# VFD25650.net
KiCad netlist of a schematic drawn in Altium Designer
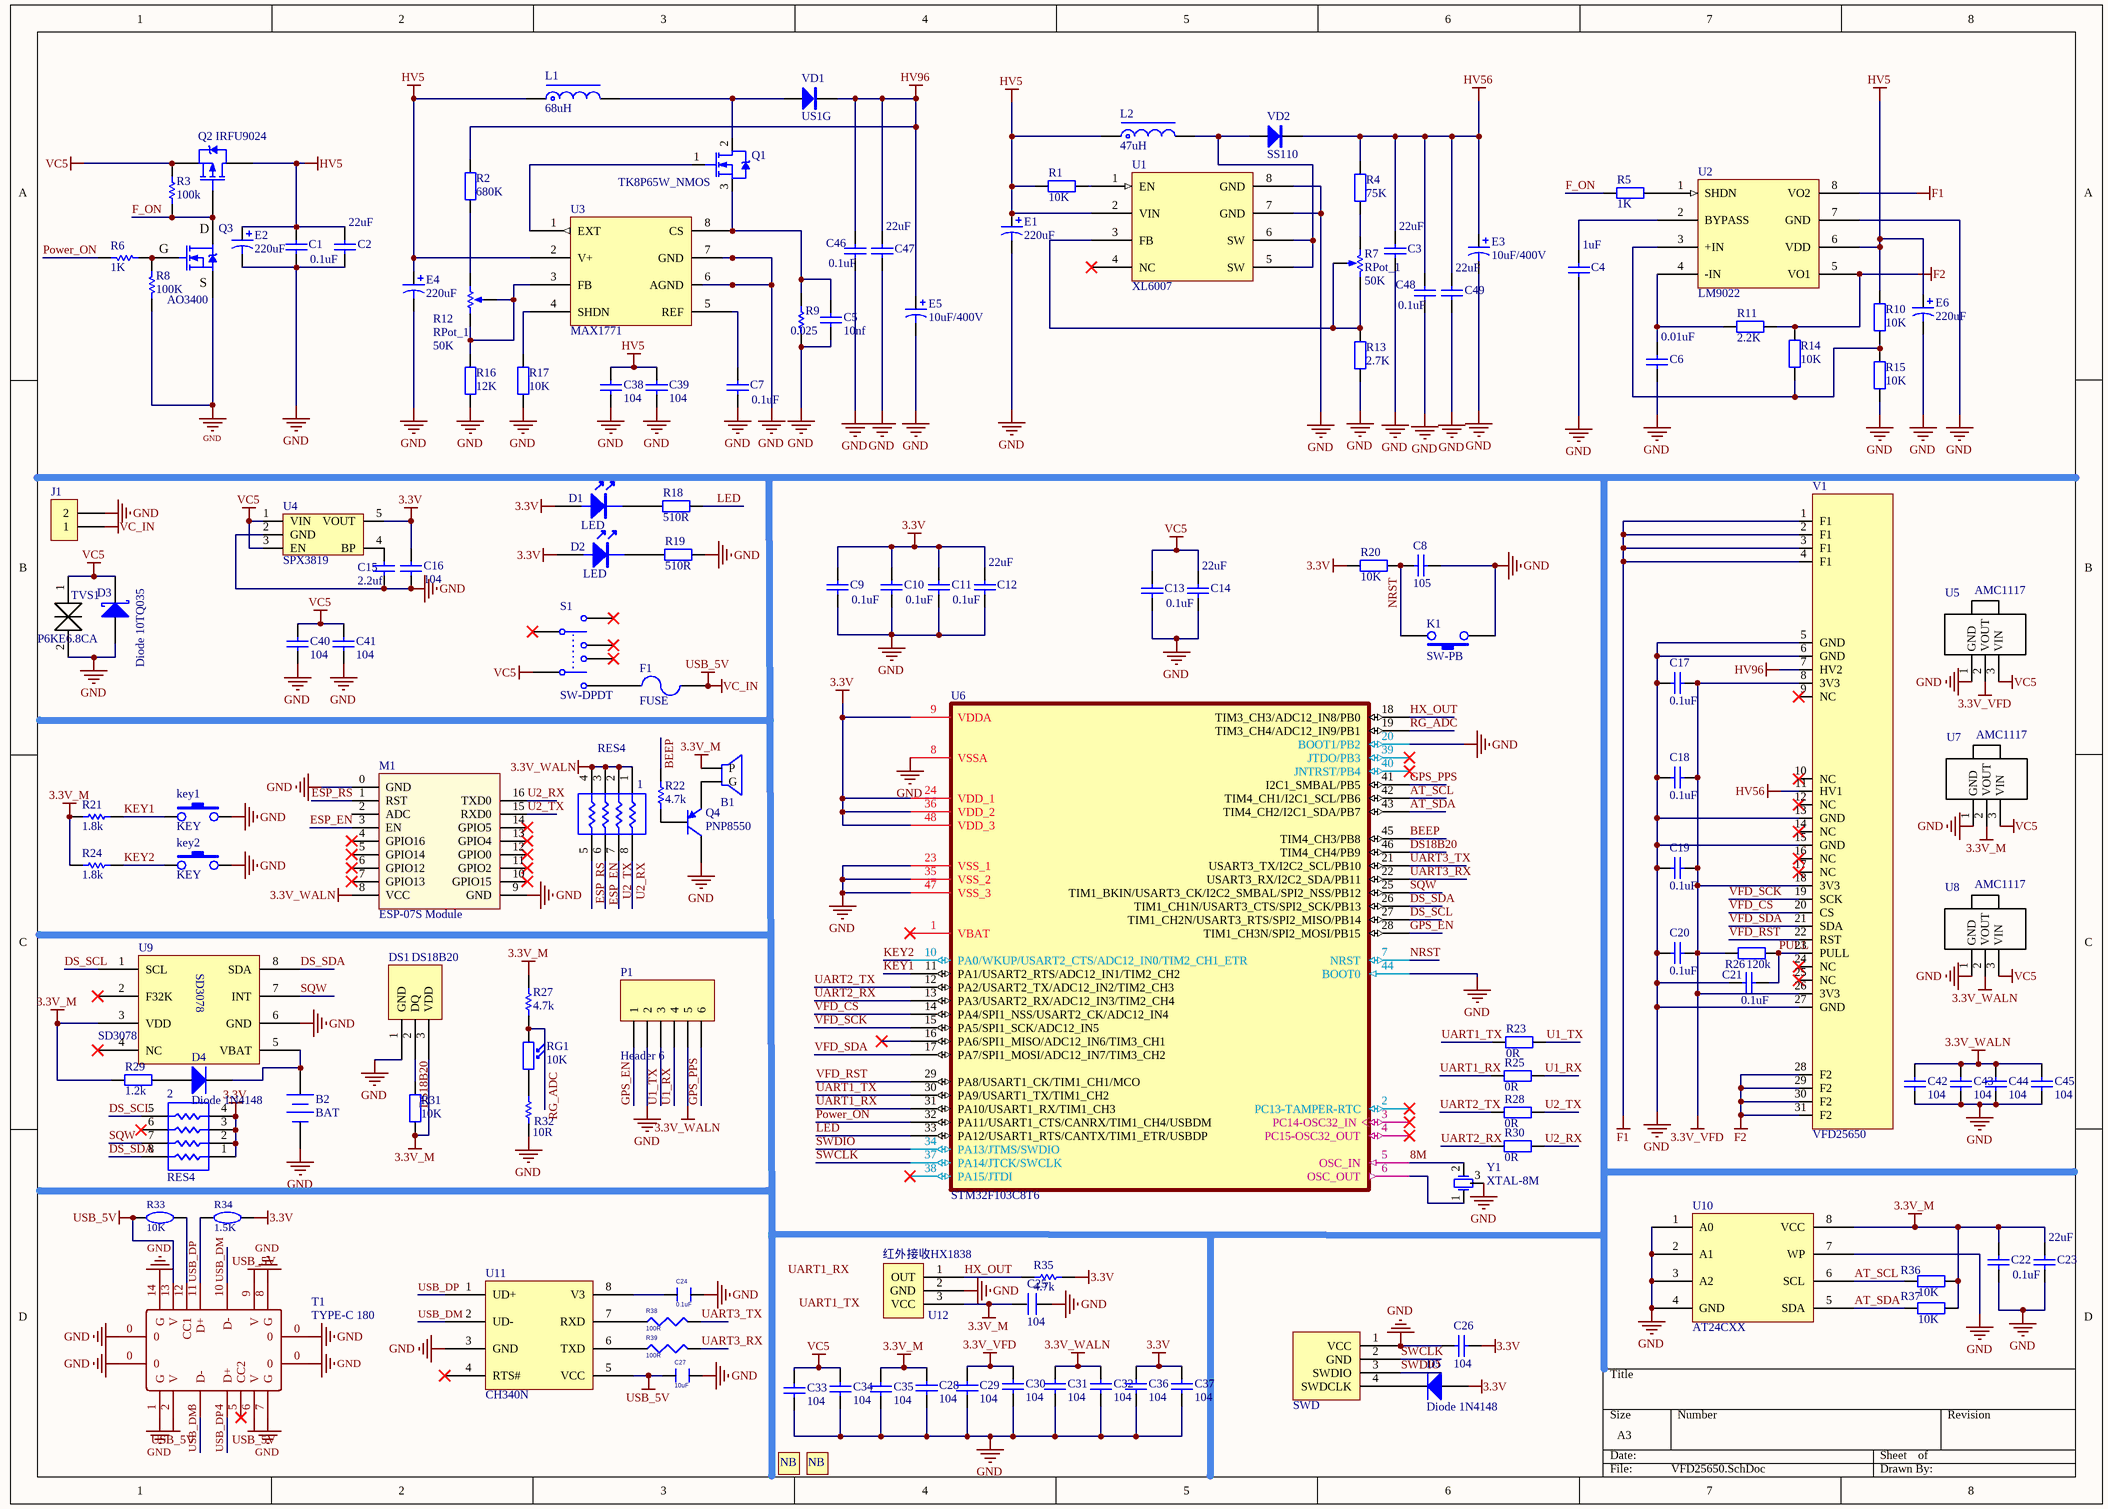
[diagram p0: VFD25650.SchDoc]

(export (version "E")
  (design (tool "Eeschema 10.0.6"))
  (components
    (comp (ref "1") (value "RES4") (footprint "0603RES") (libsource (lib "鲸落") (part "RES4")))
    (comp (ref "2") (value "RES4") (footprint "0603RES") (libsource (lib "鲸落") (part "RES4")))
    (comp (ref "B1") (value "BEEP") (footprint "BELL-SMALL") (libsource (lib "Mlia") (part "BEEP")))
    (comp (ref "B2") (value "BAT") (footprint "CR2032_B") (libsource (lib "Mlia") (part "BAT")))
    (comp (ref "C1")
      (value "0.1uF")
      (footprint "0603C")
      (description "Capacitor")
      (fields (field (name "Comment") "Cap") (field (name "PUBLISHER") "Altium Limited"))
      (libsource (lib "Miscellaneous Devices") (part "Cap"))
    )
    (comp (ref "C2")
      (value "22uF")
      (footprint "0603C")
      (description "Capacitor")
      (fields (field (name "Comment") "Cap") (field (name "PUBLISHER") "Altium Limited"))
      (libsource (lib "Miscellaneous Devices") (part "Cap"))
    )
    (comp (ref "C3")
      (value "22uF")
      (footprint "0603C")
      (description "Capacitor")
      (fields (field (name "Comment") "Cap") (field (name "PUBLISHER") "Altium Limited"))
      (libsource (lib "Miscellaneous Devices") (part "Cap"))
    )
    (comp (ref "C4")
      (value "1uF")
      (footprint "0603C")
      (description "Capacitor")
      (fields (field (name "Comment") "Cap") (field (name "PUBLISHER") "Altium Limited"))
      (libsource (lib "Miscellaneous Devices") (part "Cap"))
    )
    (comp (ref "C5")
      (value "10nf")
      (footprint "C 0603")
      (description "贴片电容")
      (fields (field (name "PUBLISHER") "Altium Limited"))
      (libsource (lib "Miscellaneous Devices") (part "Cap"))
    )
    (comp (ref "C6")
      (value "0.01uF")
      (footprint "0603C")
      (description "Capacitor")
      (fields (field (name "Comment") "Cap") (field (name "PUBLISHER") "Altium Limited"))
      (libsource (lib "Miscellaneous Devices") (part "Cap"))
    )
    (comp (ref "C7")
      (value "0.1uF")
      (footprint "0603C")
      (description "Capacitor")
      (fields (field (name "Comment") "Cap") (field (name "PUBLISHER") "Altium Limited"))
      (libsource (lib "Miscellaneous Devices") (part "Cap"))
    )
    (comp (ref "C8")
      (value "105")
      (footprint "0603C")
      (description "Capacitor")
      (fields (field (name "PUBLISHER") "Altium Limited"))
      (libsource (lib "STM32F103C8T6") (part "Cap"))
    )
    (comp (ref "C9")
      (value "0.1uF")
      (footprint "0603C")
      (description "Capacitor")
      (fields (field (name "Comment") "Cap") (field (name "PUBLISHER") "Altium Limited"))
      (libsource (lib "Miscellaneous Devices") (part "Cap"))
    )
    (comp (ref "C10")
      (value "0.1uF")
      (footprint "0603C")
      (description "Capacitor")
      (fields (field (name "Comment") "Cap") (field (name "PUBLISHER") "Altium Limited"))
      (libsource (lib "Miscellaneous Devices") (part "Cap"))
    )
    (comp (ref "C11")
      (value "0.1uF")
      (footprint "0603C")
      (description "Capacitor")
      (fields (field (name "Comment") "Cap") (field (name "PUBLISHER") "Altium Limited"))
      (libsource (lib "Miscellaneous Devices") (part "Cap"))
    )
    (comp (ref "C12")
      (value "22uF")
      (footprint "0603C")
      (description "Capacitor")
      (fields (field (name "Comment") "Cap") (field (name "PUBLISHER") "Altium Limited"))
      (libsource (lib "Miscellaneous Devices") (part "Cap"))
    )
    (comp (ref "C13")
      (value "0.1uF")
      (footprint "0603C")
      (description "Capacitor")
      (fields (field (name "Comment") "Cap") (field (name "PUBLISHER") "Altium Limited"))
      (libsource (lib "Miscellaneous Devices") (part "Cap"))
    )
    (comp (ref "C14")
      (value "22uF")
      (footprint "0603C")
      (description "Capacitor")
      (fields (field (name "Comment") "Cap") (field (name "PUBLISHER") "Altium Limited"))
      (libsource (lib "Miscellaneous Devices") (part "Cap"))
    )
    (comp (ref "C15")
      (value "2.2uf")
      (footprint "0603C")
      (description "Polarized Capacitor (Radial)")
      (fields (field (name "Comment") "Cap") (field (name "PUBLISHER") "Altium Limited"))
      (libsource (lib "Fantasy") (part "Cap"))
    )
    (comp (ref "C16")
      (value "104")
      (footprint "0603C")
      (description "Polarized Capacitor (Radial)")
      (fields (field (name "Comment") "Cap") (field (name "PUBLISHER") "Altium Limited"))
      (libsource (lib "Fantasy") (part "Cap"))
    )
    (comp (ref "C17")
      (value "0.1uF")
      (footprint "0603C")
      (description "Capacitor")
      (fields (field (name "Comment") "Cap") (field (name "PUBLISHER") "Altium Limited"))
      (libsource (lib "Miscellaneous Devices") (part "Cap"))
    )
    (comp (ref "C18")
      (value "0.1uF")
      (footprint "0603C")
      (description "Capacitor")
      (fields (field (name "Comment") "Cap") (field (name "PUBLISHER") "Altium Limited"))
      (libsource (lib "Miscellaneous Devices") (part "Cap"))
    )
    (comp (ref "C19")
      (value "0.1uF")
      (footprint "0603C")
      (description "Capacitor")
      (fields (field (name "Comment") "Cap") (field (name "PUBLISHER") "Altium Limited"))
      (libsource (lib "Miscellaneous Devices") (part "Cap"))
    )
    (comp (ref "C20")
      (value "0.1uF")
      (footprint "0603C")
      (description "Capacitor")
      (fields (field (name "Comment") "Cap") (field (name "PUBLISHER") "Altium Limited"))
      (libsource (lib "Miscellaneous Devices") (part "Cap"))
    )
    (comp (ref "C21")
      (value "0.1uF")
      (footprint "0603C")
      (description "Capacitor")
      (fields (field (name "Comment") "Cap") (field (name "PUBLISHER") "Altium Limited"))
      (libsource (lib "Miscellaneous Devices") (part "Cap"))
    )
    (comp (ref "C22")
      (value "0.1uF")
      (footprint "0603C")
      (description "Capacitor")
      (fields (field (name "Comment") "Cap") (field (name "PUBLISHER") "Altium Limited"))
      (libsource (lib "Miscellaneous Devices") (part "Cap"))
    )
    (comp (ref "C23")
      (value "22uF")
      (footprint "0603C")
      (description "Capacitor")
      (fields (field (name "Comment") "Cap") (field (name "PUBLISHER") "Altium Limited"))
      (libsource (lib "Miscellaneous Devices") (part "Cap"))
    )
    (comp (ref "C24")
      (value "0.1uF")
      (footprint "C 0603")
      (description "CAP ±20%/6.3V/X5R/SMT0402")
      (libsource (lib "*") (part "CAPACITOR"))
    )
    (comp (ref "C25") (value "104") (footprint "0603C") (libsource (lib "Mlia") (part "0603C")))
    (comp (ref "C26")
      (value "104")
      (footprint "0603C")
      (description "Capacitor")
      (fields (field (name "PUBLISHER") "Altium Limited"))
      (libsource (lib "STM32F103C8T6") (part "Cap"))
    )
    (comp (ref "C27")
      (value "10uF")
      (footprint "C 0603")
      (description "CAP ±20%/10V/X5R/SMT0603")
      (libsource (lib "*") (part "CAPACITOR"))
    )
    (comp (ref "C28")
      (value "104")
      (footprint "0603C")
      (description "无极性电容")
      (fields (field (name "Comment") "Cap") (field (name "PUBLISHER") "Altium Limited"))
      (libsource (lib "Fszhang") (part "Cap"))
    )
    (comp (ref "C29")
      (value "104")
      (footprint "0603C")
      (description "无极性电容")
      (fields (field (name "Comment") "Cap") (field (name "PUBLISHER") "Altium Limited"))
      (libsource (lib "Fszhang") (part "Cap"))
    )
    (comp (ref "C30")
      (value "104")
      (footprint "0603C")
      (description "无极性电容")
      (fields (field (name "Comment") "Cap") (field (name "PUBLISHER") "Altium Limited"))
      (libsource (lib "Fszhang") (part "Cap"))
    )
    (comp (ref "C31")
      (value "104")
      (footprint "0603C")
      (description "无极性电容")
      (fields (field (name "Comment") "Cap") (field (name "PUBLISHER") "Altium Limited"))
      (libsource (lib "Fszhang") (part "Cap"))
    )
    (comp (ref "C32")
      (value "104")
      (footprint "0603C")
      (description "无极性电容")
      (fields (field (name "Comment") "Cap") (field (name "PUBLISHER") "Altium Limited"))
      (libsource (lib "Fszhang") (part "Cap"))
    )
    (comp (ref "C33")
      (value "104")
      (footprint "0603C")
      (description "无极性电容")
      (fields (field (name "Comment") "Cap") (field (name "PUBLISHER") "Altium Limited"))
      (libsource (lib "Fszhang") (part "Cap"))
    )
    (comp (ref "C34")
      (value "104")
      (footprint "0603C")
      (description "无极性电容")
      (fields (field (name "Comment") "Cap") (field (name "PUBLISHER") "Altium Limited"))
      (libsource (lib "Fszhang") (part "Cap"))
    )
    (comp (ref "C35")
      (value "104")
      (footprint "0603C")
      (description "无极性电容")
      (fields (field (name "Comment") "Cap") (field (name "PUBLISHER") "Altium Limited"))
      (libsource (lib "Fszhang") (part "Cap"))
    )
    (comp (ref "C36")
      (value "104")
      (footprint "0603C")
      (description "无极性电容")
      (fields (field (name "Comment") "Cap") (field (name "PUBLISHER") "Altium Limited"))
      (libsource (lib "Fszhang") (part "Cap"))
    )
    (comp (ref "C37")
      (value "104")
      (footprint "0603C")
      (description "无极性电容")
      (fields (field (name "Comment") "Cap") (field (name "PUBLISHER") "Altium Limited"))
      (libsource (lib "Fszhang") (part "Cap"))
    )
    (comp (ref "C38")
      (value "104")
      (footprint "0603C")
      (description "无极性电容")
      (fields (field (name "Comment") "Cap") (field (name "PUBLISHER") "Altium Limited"))
      (libsource (lib "Fszhang") (part "Cap"))
    )
    (comp (ref "C39")
      (value "104")
      (footprint "0603C")
      (description "无极性电容")
      (fields (field (name "Comment") "Cap") (field (name "PUBLISHER") "Altium Limited"))
      (libsource (lib "Fszhang") (part "Cap"))
    )
    (comp (ref "C40")
      (value "104")
      (footprint "0603C")
      (description "无极性电容")
      (fields (field (name "Comment") "Cap") (field (name "PUBLISHER") "Altium Limited"))
      (libsource (lib "Fszhang") (part "Cap"))
    )
    (comp (ref "C41")
      (value "104")
      (footprint "0603C")
      (description "无极性电容")
      (fields (field (name "Comment") "Cap") (field (name "PUBLISHER") "Altium Limited"))
      (libsource (lib "Fszhang") (part "Cap"))
    )
    (comp (ref "C42")
      (value "104")
      (footprint "0603C")
      (description "无极性电容")
      (fields (field (name "Comment") "Cap") (field (name "PUBLISHER") "Altium Limited"))
      (libsource (lib "Fszhang") (part "Cap"))
    )
    (comp (ref "C43")
      (value "104")
      (footprint "0603C")
      (description "无极性电容")
      (fields (field (name "Comment") "Cap") (field (name "PUBLISHER") "Altium Limited"))
      (libsource (lib "Fszhang") (part "Cap"))
    )
    (comp (ref "C44")
      (value "104")
      (footprint "0603C")
      (description "无极性电容")
      (fields (field (name "Comment") "Cap") (field (name "PUBLISHER") "Altium Limited"))
      (libsource (lib "Fszhang") (part "Cap"))
    )
    (comp (ref "C45")
      (value "104")
      (footprint "0603C")
      (description "无极性电容")
      (fields (field (name "Comment") "Cap") (field (name "PUBLISHER") "Altium Limited"))
      (libsource (lib "Fszhang") (part "Cap"))
    )
    (comp (ref "C46")
      (value "0.1uF")
      (footprint "0805C")
      (description "Capacitor")
      (fields (field (name "Comment") "Cap") (field (name "PUBLISHER") "Altium Limited"))
      (libsource (lib "Miscellaneous Devices") (part "Cap"))
    )
    (comp (ref "C47")
      (value "22uF")
      (footprint "0805C")
      (description "Capacitor")
      (fields (field (name "Comment") "Cap") (field (name "PUBLISHER") "Altium Limited"))
      (libsource (lib "Miscellaneous Devices") (part "Cap"))
    )
    (comp (ref "C48")
      (value "0.1uF")
      (footprint "0805C")
      (description "Capacitor")
      (fields (field (name "Comment") "Cap") (field (name "PUBLISHER") "Altium Limited"))
      (libsource (lib "Miscellaneous Devices") (part "Cap"))
    )
    (comp (ref "C49")
      (value "22uF")
      (footprint "0805C")
      (description "Capacitor")
      (fields (field (name "Comment") "Cap") (field (name "PUBLISHER") "Altium Limited"))
      (libsource (lib "Miscellaneous Devices") (part "Cap"))
    )
    (comp (ref "D1") (value "LED") (footprint "LED 0805B") (libsource (lib "STM32F103C8T6") (part "LED")))
    (comp (ref "D2") (value "LED") (footprint "LED 0603R") (libsource (lib "STM32F103C8T6") (part "LED")))
    (comp (ref "D3")
      (value "Diode 10TQ035")
      (footprint "SOD-123")
      (description "Schottky Rectifier")
      (fields (field (name "PUBLISHER") "Altium Limited"))
      (libsource (lib "Miscellaneous Devices") (part "Diode 10TQ035"))
    )
    (comp (ref "D4")
      (value "Diode 1N4148")
      (footprint "SOD-323")
      (description "High Conductance Fast Diode")
      (fields (field (name "PUBLISHER") "Altium Limited"))
      (libsource (lib "LONG_lclr") (part "Diode 1N4148"))
    )
    (comp (ref "D5")
      (value "Diode 1N4148")
      (footprint "SOD-323")
      (description "High Conductance Fast Diode")
      (fields (field (name "PUBLISHER") "Altium Limited"))
      (libsource (lib "LONG_lclr") (part "Diode 1N4148"))
    )
    (comp (ref "DS1")
      (value "DS18B20")
      (footprint "HDR-1X3")
      (description "温度传感器")
      (libsource (lib "Fszhang") (part "DS18B20"))
    )
    (comp (ref "E1")
      (value "220uF")
      (footprint "CM D(6.3*5.4)")
      (description "Polarized Capacitor (Radial)")
      (fields (field (name "Comment") "Cap Pol1") (field (name "PUBLISHER") "Altium Limited"))
      (libsource (lib "Miscellaneous Devices") (part "Cap Pol1"))
    )
    (comp (ref "E2")
      (value "220uF")
      (footprint "CM D(6.3*5.4)")
      (description "Polarized Capacitor (Radial)")
      (fields (field (name "Comment") "Cap Pol1") (field (name "PUBLISHER") "Altium Limited"))
      (libsource (lib "Miscellaneous Devices") (part "Cap Pol1"))
    )
    (comp (ref "E3")
      (value "10uF/400V")
      (footprint "CM D(6.3*5.4)")
      (description "Polarized Capacitor (Radial)")
      (fields (field (name "Comment") "Cap Pol1") (field (name "PUBLISHER") "Altium Limited"))
      (libsource (lib "Miscellaneous Devices") (part "Cap Pol1"))
    )
    (comp (ref "E4")
      (value "220uF")
      (footprint "CM D(6.3*5.4)")
      (description "Polarized Capacitor (Radial)")
      (fields (field (name "Comment") "Cap Pol1") (field (name "PUBLISHER") "Altium Limited"))
      (libsource (lib "Miscellaneous Devices") (part "Cap Pol1"))
    )
    (comp (ref "E5")
      (value "10uF/400V")
      (footprint "CM D(6.3*5.4)")
      (description "Polarized Capacitor (Radial)")
      (fields (field (name "Comment") "Cap Pol1") (field (name "PUBLISHER") "Altium Limited"))
      (libsource (lib "Miscellaneous Devices") (part "Cap Pol1"))
    )
    (comp (ref "E6")
      (value "220uF")
      (footprint "CM D(6.3*5.4)")
      (description "Polarized Capacitor (Radial)")
      (fields (field (name "Comment") "Cap Pol1") (field (name "PUBLISHER") "Altium Limited"))
      (libsource (lib "Miscellaneous Devices") (part "Cap Pol1"))
    )
    (comp (ref "F1") (value "FUSE") (footprint "FU 0805") (libsource (lib "Mlia") (part "FUSE")))
    (comp (ref "J1")
      (value "CON2")
      (footprint "DC-012")
      (description "Connector")
      (libsource (lib "*") (part "CON2"))
    )
    (comp (ref "K1") (value "SW-PB") (footprint "KEY_M") (libsource (lib "*") (part "SW-PB")))
    (comp (ref "key1") (value "KEY") (footprint "TSW DIP-6*6*7_V") (libsource (lib "LONG_lclr") (part "KEY")))
    (comp (ref "key2") (value "KEY") (footprint "TSW DIP-6*6*7_V") (libsource (lib "LONG_lclr") (part "KEY")))
    (comp (ref "L1")
      (value "68uH")
      (footprint "CDRH73")
      (description "工字电感")
      (fields (field (name "版权归属") "源创客"))
      (libsource (lib "3D Mode") (part "L-PK"))
    )
    (comp (ref "L2")
      (value "47uH")
      (footprint "CDRH73")
      (description "工字电感")
      (fields (field (name "版权归属") "源创客"))
      (libsource (lib "3D Mode") (part "L-PK"))
    )
    (comp (ref "M1")
      (value "ESP-07S Module")
      (footprint "ESP-07S Module")
      (libsource (lib "LONG_lclr") (part "ESP-07S Module"))
    )
    (comp (ref "P1")
      (value "Header 6")
      (footprint "LONG_lclr:1.25-6p")
      (description "Header, 6-Pin")
      (fields (field (name "PUBLISHER") "Altium Limited"))
      (libsource (lib "Miscellaneous Connectors") (part "Header 6"))
    )
    (comp (ref "picture1") (value "图标") (footprint "rapter") (libsource (lib "LONG_lclr") (part "SP")))
    (comp (ref "picture2") (value "图标") (footprint "LCL") (libsource (lib "LONG_lclr") (part "SP")))
    (comp (ref "Q1") (value "TK8P65W_NMOS") (footprint "TO252") (libsource (lib "Mlia") (part "IR7843_NMOS")))
    (comp (ref "Q2")
      (value "IRFU9024")
      (footprint "TO252 - duplicate")
      (description "P-Channel Power MOSFET")
      (fields (field (name "PUBLISHER") "Altium Limited"))
      (libsource (lib "LONG_lclr") (part "PMOS-2"))
    )
    (comp (ref "Q3")
      (value "AO3400")
      (footprint "MMBT3906")
      (description "N沟场效应管 贴片SOT23-3")
      (fields (field (name "版权归属") "源创客"))
      (libsource (lib "3D Mode") (part "2SK3615"))
    )
    (comp (ref "Q4") (value "PNP8550") (footprint "NPN8050 SOT23R") (libsource (lib "Mlia") (part "PNP8550")))
    (comp (ref "R1")
      (value "10K")
      (footprint "0805R")
      (description "Resistor")
      (fields (field (name "PUBLISHER") "Altium Limited"))
      (libsource (lib "STM32F103C8T6") (part "Res2"))
    )
    (comp (ref "R2")
      (value "680K")
      (footprint "0805R")
      (description "Resistor")
      (fields (field (name "PUBLISHER") "Altium Limited"))
      (libsource (lib "") (part "Res2_3"))
    )
    (comp (ref "R3") (value "100k") (footprint "0805R") (libsource (lib "Mlia") (part "0603r")))
    (comp (ref "R4")
      (value "75K")
      (footprint "0805R")
      (description "Resistor")
      (fields (field (name "PUBLISHER") "Altium Limited"))
      (libsource (lib "") (part "Res2_3"))
    )
    (comp (ref "R5")
      (value "1K")
      (footprint "0805R")
      (description "Resistor")
      (fields (field (name "PUBLISHER") "Altium Limited"))
      (libsource (lib "STM32F103C8T6") (part "Res2"))
    )
    (comp (ref "R6")
      (value "1K")
      (footprint "0603R")
      (description "贴片电阻 0603")
      (fields (field (name "PUBLISHER") "Altium Limited"))
      (libsource (lib "Miscellaneous Devices") (part "Res1"))
    )
    (comp (ref "R7")
      (value "RPot_1")
      (footprint "RPart")
      (description "Potentiometer")
      (fields (field (name "ALTIUM_VALUE") "50K") (field (name "PUBLISHER") "Altium Limited"))
      (libsource (lib "LONG_lclr") (part "RPot_1"))
    )
    (comp (ref "R8")
      (value "100K")
      (footprint "0603R")
      (description "贴片电阻 0603")
      (fields (field (name "PUBLISHER") "Altium Limited"))
      (libsource (lib "Miscellaneous Devices") (part "Res1"))
    )
    (comp (ref "R9")
      (value "0.025")
      (footprint "RES 1206")
      (description "贴片电阻")
      (fields (field (name "PUBLISHER") "Altium Limited"))
      (libsource (lib "Miscellaneous Devices") (part "Res1"))
    )
    (comp (ref "R10")
      (value "10K")
      (footprint "0805R")
      (description "Resistor")
      (fields (field (name "PUBLISHER") "Altium Limited"))
      (libsource (lib "") (part "Res2_3"))
    )
    (comp (ref "R11")
      (value "2.2K")
      (footprint "0805R")
      (description "Resistor")
      (fields (field (name "PUBLISHER") "Altium Limited"))
      (libsource (lib "STM32F103C8T6") (part "Res2"))
    )
    (comp (ref "R12")
      (value "RPot_1")
      (footprint "RPart")
      (description "Potentiometer")
      (fields (field (name "ALTIUM_VALUE") "50K") (field (name "PUBLISHER") "Altium Limited"))
      (libsource (lib "LONG_lclr") (part "RPot_1"))
    )
    (comp (ref "R13")
      (value "2.7K")
      (footprint "0805R")
      (description "Resistor")
      (fields (field (name "PUBLISHER") "Altium Limited"))
      (libsource (lib "") (part "Res2_3"))
    )
    (comp (ref "R14")
      (value "10K")
      (footprint "0805R")
      (description "Resistor")
      (fields (field (name "PUBLISHER") "Altium Limited"))
      (libsource (lib "") (part "Res2_3"))
    )
    (comp (ref "R15")
      (value "10K")
      (footprint "0805R")
      (description "Resistor")
      (fields (field (name "PUBLISHER") "Altium Limited"))
      (libsource (lib "") (part "Res2_2"))
    )
    (comp (ref "R16")
      (value "12K")
      (footprint "0805R")
      (description "Resistor")
      (fields (field (name "PUBLISHER") "Altium Limited"))
      (libsource (lib "") (part "Res2_3"))
    )
    (comp (ref "R17")
      (value "10K")
      (footprint "0603R")
      (description "Resistor")
      (fields (field (name "PUBLISHER") "Altium Limited"))
      (libsource (lib "") (part "Res2_2"))
    )
    (comp (ref "R18")
      (value "510R")
      (footprint "0603R")
      (description "Resistor")
      (fields (field (name "PUBLISHER") "Altium Limited"))
      (libsource (lib "") (part "Res2_1"))
    )
    (comp (ref "R19")
      (value "510R")
      (footprint "0603R")
      (description "Resistor")
      (fields (field (name "PUBLISHER") "Altium Limited"))
      (libsource (lib "") (part "Res2_1"))
    )
    (comp (ref "R20")
      (value "10K")
      (footprint "0603R")
      (description "Resistor")
      (fields (field (name "PUBLISHER") "Altium Limited"))
      (libsource (lib "STM32F103C8T6") (part "Res2"))
    )
    (comp (ref "R21") (value "1.8k") (footprint "0603R") (libsource (lib "Mlia") (part "0603r")))
    (comp (ref "R22") (value "4.7k") (footprint "0603R") (libsource (lib "Mlia") (part "0603r")))
    (comp (ref "R23")
      (value "0R")
      (footprint "0805R")
      (description "Resistor")
      (fields (field (name "PUBLISHER") "Altium Limited"))
      (libsource (lib "") (part "Res2_1"))
    )
    (comp (ref "R24") (value "1.8k") (footprint "0603R") (libsource (lib "Mlia") (part "0603r")))
    (comp (ref "R25")
      (value "0R")
      (footprint "0805R")
      (description "Resistor")
      (fields (field (name "PUBLISHER") "Altium Limited"))
      (libsource (lib "") (part "Res2_1"))
    )
    (comp (ref "R26")
      (value "120k")
      (footprint "R 0603")
      (description "Resistor")
      (fields (field (name "PUBLISHER") "Altium Limited"))
      (libsource (lib "") (part "Res2_1"))
    )
    (comp (ref "R27") (value "4.7k") (footprint "0603R") (libsource (lib "Mlia") (part "0603r")))
    (comp (ref "R28")
      (value "0R")
      (footprint "0805R")
      (description "Resistor")
      (fields (field (name "PUBLISHER") "Altium Limited"))
      (libsource (lib "") (part "Res2_1"))
    )
    (comp (ref "R29")
      (value "1.2k")
      (footprint "0603R")
      (description "贴片电阻")
      (fields (field (name "Comment") "Res1") (field (name "PUBLISHER") "Altium Limited"))
      (libsource (lib "") (part "Res1_1"))
    )
    (comp (ref "R30")
      (value "0R")
      (footprint "0805R")
      (description "Resistor")
      (fields (field (name "PUBLISHER") "Altium Limited"))
      (libsource (lib "") (part "Res2_1"))
    )
    (comp (ref "R31")
      (value "10K")
      (footprint "0603R")
      (description "贴片电阻")
      (fields (field (name "Comment") "Res1") (field (name "PUBLISHER") "Altium Limited"))
      (libsource (lib "Fszhang") (part "Res1"))
    )
    (comp (ref "R32") (value "10R") (footprint "0603R") (libsource (lib "Mlia") (part "0603r")))
    (comp (ref "R33")
      (value "1A保险丝")
      (footprint "R 0603")
      (fields (field (name "COMMENT_1") "10K") (field (name "PUBLISHER") "Altium Limited"))
      (libsource (lib "altium-import") (part "root_2_10K_"))
    )
    (comp (ref "R34")
      (value "1K")
      (footprint "R 0603")
      (fields (field (name "COMMENT_1") "1.5K") (field (name "PUBLISHER") "Altium Limited"))
      (libsource (lib "altium-import") (part "root_2_1.5K_"))
    )
    (comp (ref "R35") (value "4.7k") (footprint "0603R") (libsource (lib "Mlia") (part "0603r")))
    (comp (ref "R36")
      (value "10K")
      (footprint "0603R")
      (description "Resistor")
      (fields (field (name "PUBLISHER") "Altium Limited"))
      (libsource (lib "STM32F103C8T6") (part "Res2"))
    )
    (comp (ref "R37")
      (value "10K")
      (footprint "0603R")
      (description "Resistor")
      (fields (field (name "PUBLISHER") "Altium Limited"))
      (libsource (lib "STM32F103C8T6") (part "Res2"))
    )
    (comp (ref "R38")
      (value "100R")
      (footprint "R 0603")
      (description "RES 1/16W 5% SMT0402")
      (libsource (lib "*") (part "R_Dup1"))
    )
    (comp (ref "R39")
      (value "100R")
      (footprint "R 0603")
      (description "RES 1/16W 5% SMT0402")
      (libsource (lib "*") (part "R_Dup1"))
    )
    (comp (ref "RG1")
      (value "10K")
      (footprint "RG5528")
      (description "光敏电阻")
      (fields (field (name "版权归属") "源创客"))
      (libsource (lib "3D Mode") (part "RG5528"))
    )
    (comp (ref "S1")
      (value "SW-DPDT")
      (footprint "SWitch - duplicate1")
      (description "Double-Pole, Double-Throw Switch")
      (fields (field (name "PUBLISHER") "Altium Limited"))
      (libsource (lib "鲸落") (part "SW-DPDT"))
    )
    (comp (ref "SWD1") (value "SWD") (footprint "1.25-4p") (libsource (lib "自创") (part "SWD")))
    (comp (ref "T1")
      (value "TYPE-C 180")
      (footprint "type-c 180")
      (libsource (lib "LONG_lclr") (part "TYPE-C 180"))
    )
    (comp (ref "TVS1") (value "P6KE6.8CA") (footprint "SMB") (libsource (lib "VFDClock") (part "P6KE6.8CA")))
    (comp (ref "U1") (value "XL6007") (footprint "SOP8_N") (libsource (lib "LONG_lclr") (part "XL6007")))
    (comp (ref "U2") (value "LM9022") (footprint "SOP8_N") (libsource (lib "LONG_lclr") (part "LM9022")))
    (comp (ref "U3") (value "MAX1771") (footprint "SOP8_N") (libsource (lib "LONG_lclr") (part "MAX1771")))
    (comp (ref "U4")
      (value "SPX3819")
      (footprint "SOT23-5N")
      (description "3.3V超低压差LDO")
      (libsource (lib "Fantasy") (part "RT9193-33"))
    )
    (comp (ref "U5")
      (value "AMC1117")
      (footprint "AMS1117_SOT223")
      (libsource (lib "VFDClock") (part "AMC1117"))
    )
    (comp (ref "U6")
      (value "STM32F103C8T6")
      (footprint "LQFP48 7X7_L")
      (description "STM32 ARM-based 32-bit MCU with 64 Kbytes Flash, 48-pin LQFP, Industrial Temperature")
      (fields (field (name "PUBLISHER") "*"))
      (libsource (lib "stm32") (part "STM32F103C8T6"))
    )
    (comp (ref "U7")
      (value "AMC1117")
      (footprint "AMS1117_SOT223")
      (libsource (lib "VFDClock") (part "AMC1117"))
    )
    (comp (ref "U8")
      (value "AMC1117")
      (footprint "AMS1117_SOT223")
      (libsource (lib "VFDClock") (part "AMC1117"))
    )
    (comp (ref "U9") (value "SD3078") (footprint "SOP8W_L") (libsource (lib "LONG_lclr") (part "SD3078")))
    (comp (ref "U10") (value "AT24CXX") (footprint "SOP8_N") (libsource (lib "LONG_lclr") (part "AT24CXX")))
    (comp (ref "U11") (value "CH340N") (footprint "SOP8_N") (libsource (lib "LONG_lclr") (part "CH340N")))
    (comp (ref "U12")
      (value "红外接收HX1838")
      (footprint "红外HX1838")
      (libsource (lib "Mlia") (part "红外接收HX1838"))
    )
    (comp (ref "V1")
      (value "VFD25650")
      (footprint "VFD-25650")
      (libsource (lib "LONG_lclr") (part "VFD25650"))
    )
    (comp (ref "VD1")
      (value "US1G")
      (footprint "SMA")
      (description "肖特基二极管")
      (fields (field (name "版权归属") "源创客"))
      (libsource (lib "3D Mode") (part "SS14"))
    )
    (comp (ref "VD2")
      (value "SS110")
      (footprint "SMA")
      (description "肖特基二极管")
      (fields (field (name "版权归属") "源创客"))
      (libsource (lib "3D Mode") (part "SS14"))
    )
    (comp (ref "Y1") (value "XTAL-8M") (footprint "XTAL_8M") (libsource (lib "Mlia") (part "XTAL-8M")))
  )
  (nets
    (net (code "1") (name "/8M") (class "Default")
      (node (ref "U6") (pin "5") (pinfunction "OSC_IN_5") (pintype "input"))
      (node (ref "Y1") (pin "2") (pinfunction "OSC2_2") (pintype "passive"))
    )
    (net (code "2") (name "/AT_SCL") (class "Default")
      (node (ref "R36") (pin "2") (pinfunction "2_2") (pintype "passive"))
      (node (ref "U10") (pin "6") (pinfunction "SCL_6") (pintype "passive"))
      (node (ref "U6") (pin "42") (pinfunction "TIM4_CH1/I2C1_SCL/PB6_42") (pintype "bidirectional"))
    )
    (net (code "3") (name "/AT_SDA") (class "Default")
      (node (ref "R37") (pin "2") (pinfunction "2_2") (pintype "passive"))
      (node (ref "U10") (pin "5") (pinfunction "SDA_5") (pintype "passive"))
      (node (ref "U6") (pin "43") (pinfunction "TIM4_CH2/I2C1_SDA/PB7_43") (pintype "bidirectional"))
    )
    (net (code "4") (name "/BEEP") (class "Default")
      (node (ref "R22") (pin "2") (pinfunction "2_2") (pintype "passive"))
      (node (ref "U6") (pin "45") (pinfunction "TIM4_CH3/PB8_45") (pintype "bidirectional"))
    )
    (net (code "5") (name "/DS18B20") (class "Default")
      (node (ref "DS1") (pin "2") (pinfunction "DQ_2") (pintype "passive"))
      (node (ref "R31") (pin "1") (pinfunction "1_1") (pintype "passive"))
      (node (ref "U6") (pin "46") (pinfunction "TIM4_CH4/PB9_46") (pintype "bidirectional"))
    )
    (net (code "6") (name "/DS_SCL") (class "Default")
      (node (ref "2") (pin "5") (pinfunction "5_5") (pintype "passive"))
      (node (ref "U6") (pin "27") (pinfunction "TIM1_CH2N/USART3_RTS/SPI2_MISO/PB14_27") (pintype "bidirectional"))
      (node (ref "U9") (pin "1") (pinfunction "SCL_1") (pintype "passive"))
    )
    (net (code "7") (name "/DS_SDA") (class "Default")
      (node (ref "2") (pin "8") (pinfunction "8_8") (pintype "passive"))
      (node (ref "U6") (pin "26") (pinfunction "TIM1_CH1N/USART3_CTS/SPI2_SCK/PB13_26") (pintype "bidirectional"))
      (node (ref "U9") (pin "8") (pinfunction "SDA_8") (pintype "passive"))
    )
    (net (code "8") (name "/ESP_EN") (class "Default")
      (node (ref "1") (pin "6") (pinfunction "6_6") (pintype "passive"))
      (node (ref "M1") (pin "3") (pinfunction "EN_3") (pintype "passive"))
    )
    (net (code "9") (name "/ESP_RS") (class "Default")
      (node (ref "1") (pin "5") (pinfunction "5_5") (pintype "passive"))
      (node (ref "M1") (pin "1") (pinfunction "RST_1") (pintype "passive"))
    )
    (net (code "10") (name "/F_ON") (class "Default")
      (node (ref "Q2") (pin "1") (pinfunction "G_1") (pintype "passive"))
      (node (ref "Q3") (pin "3") (pinfunction "S_3") (pintype "passive"))
      (node (ref "R3") (pin "1") (pinfunction "1_1") (pintype "passive"))
      (node (ref "R5") (pin "2") (pinfunction "2_2") (pintype "passive"))
    )
    (net (code "11") (name "/GPS_EN") (class "Default")
      (node (ref "P1") (pin "1") (pinfunction "1_1") (pintype "passive"))
      (node (ref "U6") (pin "28") (pinfunction "TIM1_CH3N/SPI2_MOSI/PB15_28") (pintype "bidirectional"))
    )
    (net (code "12") (name "/GPS_PPS") (class "Default")
      (node (ref "P1") (pin "6") (pinfunction "6_6") (pintype "passive"))
      (node (ref "U6") (pin "41") (pinfunction "I2C1_SMBAL/PB5_41") (pintype "bidirectional"))
    )
    (net (code "13") (name "/HX_OUT") (class "Default")
      (node (ref "R35") (pin "1") (pinfunction "1_1") (pintype "passive"))
      (node (ref "U12") (pin "1") (pinfunction "OUT_1") (pintype "passive"))
      (node (ref "U6") (pin "18") (pinfunction "TIM3_CH3/ADC12_IN8/PB0_18") (pintype "bidirectional"))
    )
    (net (code "14") (name "/KEY1") (class "Default")
      (node (ref "R21") (pin "2") (pinfunction "2_2") (pintype "passive"))
      (node (ref "U6") (pin "11") (pinfunction "PA1/USART2_RTS/ADC12_IN1/TIM2_CH2_11") (pintype "bidirectional"))
      (node (ref "key1") (pin "1") (pinfunction "1_1") (pintype "passive"))
    )
    (net (code "15") (name "/KEY2") (class "Default")
      (node (ref "R24") (pin "2") (pinfunction "2_2") (pintype "passive"))
      (node (ref "U6") (pin "10") (pinfunction "PA0/WKUP/USART2_CTS/ADC12_IN0/TIM2_CH1_ETR_10") (pintype "bidirectional"))
      (node (ref "key2") (pin "1") (pinfunction "1_1") (pintype "passive"))
    )
    (net (code "16") (name "/LED") (class "Default")
      (node (ref "R18") (pin "2") (pinfunction "2_2") (pintype "passive"))
      (node (ref "U6") (pin "33") (pinfunction "PA12/USART1_RTS/CANTX/TIM1_ETR/USBDP_33") (pintype "bidirectional"))
    )
    (net (code "17") (name "/NRST") (class "Default")
      (node (ref "C8") (pin "2") (pinfunction "2_2") (pintype "passive"))
      (node (ref "K1") (pin "2") (pinfunction "2_2") (pintype "passive"))
      (node (ref "R20") (pin "1") (pinfunction "1_1") (pintype "passive"))
      (node (ref "U6") (pin "7") (pinfunction "NRST_7") (pintype "bidirectional"))
    )
    (net (code "18") (name "/PULL") (class "Default")
      (node (ref "C21") (pin "1") (pinfunction "1_1") (pintype "passive"))
      (node (ref "R26") (pin "2") (pinfunction "2_2") (pintype "passive"))
      (node (ref "V1") (pin "23") (pinfunction "PULL_23") (pintype "passive"))
    )
    (net (code "19") (name "/Power_ON") (class "Default")
      (node (ref "R6") (pin "2") (pinfunction "2_2") (pintype "passive"))
      (node (ref "U6") (pin "32") (pinfunction "PA11/USART1_CTS/CANRX/TIM1_CH4/USBDM_32") (pintype "bidirectional"))
    )
    (net (code "20") (name "/RG_ADC") (class "Default")
      (node (ref "R27") (pin "2") (pinfunction "2_2") (pintype "passive"))
      (node (ref "RG1") (pin "1") (pinfunction "1_1") (pintype "passive"))
      (node (ref "U6") (pin "19") (pinfunction "TIM3_CH4/ADC12_IN9/PB1_19") (pintype "bidirectional"))
    )
    (net (code "21") (name "/SQW") (class "Default")
      (node (ref "2") (pin "7") (pinfunction "7_7") (pintype "passive"))
      (node (ref "U6") (pin "25") (pinfunction "TIM1_BKIN/USART3_CK/I2C2_SMBAL/SPI2_NSS/PB12_25") (pintype "bidirectional"))
      (node (ref "U9") (pin "7") (pinfunction "INT_7") (pintype "passive"))
    )
    (net (code "22") (name "/SWCLK") (class "Default")
      (node (ref "SWD1") (pin "2") (pinfunction "GND_2") (pintype "passive"))
      (node (ref "U6") (pin "37") (pinfunction "PA14/JTCK/SWCLK_37") (pintype "bidirectional"))
    )
    (net (code "23") (name "/SWDIO") (class "Default")
      (node (ref "SWD1") (pin "3") (pinfunction "SWDIO_3") (pintype "passive"))
      (node (ref "U6") (pin "34") (pinfunction "PA13/JTMS/SWDIO_34") (pintype "bidirectional"))
    )
    (net (code "24") (name "/U1_RX") (class "Default")
      (node (ref "P1") (pin "4") (pinfunction "4_4") (pintype "passive"))
      (node (ref "R25") (pin "2") (pinfunction "2_2") (pintype "passive"))
    )
    (net (code "25") (name "/U1_TX") (class "Default")
      (node (ref "P1") (pin "3") (pinfunction "3_3") (pintype "passive"))
      (node (ref "R23") (pin "2") (pinfunction "2_2") (pintype "passive"))
    )
    (net (code "26") (name "/U2_RX") (class "Default")
      (node (ref "1") (pin "8") (pinfunction "8_8") (pintype "passive"))
      (node (ref "M1") (pin "16") (pinfunction "TXD0_16") (pintype "passive"))
      (node (ref "R30") (pin "2") (pinfunction "2_2") (pintype "passive"))
    )
    (net (code "27") (name "/U2_TX") (class "Default")
      (node (ref "1") (pin "7") (pinfunction "7_7") (pintype "passive"))
      (node (ref "M1") (pin "15") (pinfunction "RXD0_15") (pintype "passive"))
      (node (ref "R28") (pin "2") (pinfunction "2_2") (pintype "passive"))
    )
    (net (code "28") (name "/UART1_RX") (class "Default")
      (node (ref "R25") (pin "1") (pinfunction "1_1") (pintype "passive"))
      (node (ref "U6") (pin "31") (pinfunction "PA10/USART1_RX/TIM1_CH3_31") (pintype "bidirectional"))
    )
    (net (code "29") (name "/UART1_TX") (class "Default")
      (node (ref "R23") (pin "1") (pinfunction "1_1") (pintype "passive"))
      (node (ref "U6") (pin "30") (pinfunction "PA9/USART1_TX/TIM1_CH2_30") (pintype "bidirectional"))
    )
    (net (code "30") (name "/UART2_RX") (class "Default")
      (node (ref "R30") (pin "1") (pinfunction "1_1") (pintype "passive"))
      (node (ref "U6") (pin "13") (pinfunction "PA3/USART2_RX/ADC12_IN3/TIM2_CH4_13") (pintype "bidirectional"))
    )
    (net (code "31") (name "/UART2_TX") (class "Default")
      (node (ref "R28") (pin "1") (pinfunction "1_1") (pintype "passive"))
      (node (ref "U6") (pin "12") (pinfunction "PA2/USART2_TX/ADC12_IN2/TIM2_CH3_12") (pintype "bidirectional"))
    )
    (net (code "32") (name "/UART3_RX") (class "Default")
      (node (ref "R39") (pin "2") (pinfunction "2_2") (pintype "passive"))
      (node (ref "U6") (pin "22") (pinfunction "USART3_RX/I2C2_SDA/PB11_22") (pintype "bidirectional"))
    )
    (net (code "33") (name "/UART3_TX") (class "Default")
      (node (ref "R38") (pin "2") (pinfunction "2_2") (pintype "passive"))
      (node (ref "U6") (pin "21") (pinfunction "USART3_TX/I2C2_SCL/PB10_21") (pintype "bidirectional"))
    )
    (net (code "34") (name "/USB_DM") (class "Default")
      (node (ref "T1") (pin "10") (pinfunction "D-_10") (pintype "passive"))
      (node (ref "T1") (pin "3") (pinfunction "D-_3") (pintype "passive"))
      (node (ref "U11") (pin "2") (pinfunction "UD-_2") (pintype "passive"))
    )
    (net (code "35") (name "/USB_DP") (class "Default")
      (node (ref "R34") (pin "2") (pinfunction "2_2") (pintype "passive"))
      (node (ref "T1") (pin "11") (pinfunction "D+_11") (pintype "passive"))
      (node (ref "T1") (pin "4") (pinfunction "D+_4") (pintype "passive"))
      (node (ref "U11") (pin "1") (pinfunction "UD+_1") (pintype "passive"))
    )
    (net (code "36") (name "/VFD_CS") (class "Default")
      (node (ref "U6") (pin "14") (pinfunction "PA4/SPI1_NSS/USART2_CK/ADC12_IN4_14") (pintype "bidirectional"))
      (node (ref "V1") (pin "20") (pinfunction "CS_20") (pintype "passive"))
    )
    (net (code "37") (name "/VFD_RST") (class "Default")
      (node (ref "U6") (pin "29") (pinfunction "PA8/USART1_CK/TIM1_CH1/MCO_29") (pintype "bidirectional"))
      (node (ref "V1") (pin "22") (pinfunction "RST_22") (pintype "passive"))
    )
    (net (code "38") (name "/VFD_SCK") (class "Default")
      (node (ref "U6") (pin "15") (pinfunction "PA5/SPI1_SCK/ADC12_IN5_15") (pintype "bidirectional"))
      (node (ref "V1") (pin "19") (pinfunction "SCK_19") (pintype "passive"))
    )
    (net (code "39") (name "/VFD_SDA") (class "Default")
      (node (ref "U6") (pin "17") (pinfunction "PA7/SPI1_MOSI/ADC12_IN7/TIM3_CH2_17") (pintype "bidirectional"))
      (node (ref "V1") (pin "21") (pinfunction "SDA_21") (pintype "passive"))
    )
    (net (code "40") (name "3.3V") (class "Default")
      (node (ref "2") (pin "1") (pinfunction "1_1") (pintype "passive"))
      (node (ref "2") (pin "2") (pinfunction "2_2") (pintype "passive"))
      (node (ref "2") (pin "3") (pinfunction "3_3") (pintype "passive"))
      (node (ref "2") (pin "4") (pinfunction "4_4") (pintype "passive"))
      (node (ref "C10") (pin "2") (pinfunction "2_2") (pintype "passive"))
      (node (ref "C11") (pin "2") (pinfunction "2_2") (pintype "passive"))
      (node (ref "C12") (pin "2") (pinfunction "2_2") (pintype "passive"))
      (node (ref "C16") (pin "2") (pinfunction "2_2") (pintype "passive"))
      (node (ref "C26") (pin "2") (pinfunction "2_2") (pintype "passive"))
      (node (ref "C36") (pin "2") (pinfunction "2_2") (pintype "passive"))
      (node (ref "C37") (pin "2") (pinfunction "2_2") (pintype "passive"))
      (node (ref "C9") (pin "2") (pinfunction "2_2") (pintype "passive"))
      (node (ref "D1") (pin "1") (pinfunction "1_1") (pintype "passive"))
      (node (ref "D2") (pin "1") (pinfunction "1_1") (pintype "passive"))
      (node (ref "D5") (pin "1") (pinfunction "A_1") (pintype "passive"))
      (node (ref "R20") (pin "2") (pinfunction "2_2") (pintype "passive"))
      (node (ref "R34") (pin "1") (pinfunction "1_1") (pintype "passive"))
      (node (ref "R35") (pin "2") (pinfunction "2_2") (pintype "passive"))
      (node (ref "U4") (pin "5") (pinfunction "VOUT_5") (pintype "passive"))
      (node (ref "U6") (pin "24") (pinfunction "VDD_1_24") (pintype "power_in"))
      (node (ref "U6") (pin "36") (pinfunction "VDD_2_36") (pintype "power_in"))
      (node (ref "U6") (pin "48") (pinfunction "VDD_3_48") (pintype "power_in"))
      (node (ref "U6") (pin "9") (pinfunction "VDDA_9") (pintype "power_in"))
    )
    (net (code "41") (name "3.3V_M") (class "Default")
      (node (ref "B1") (pin "1") (pinfunction "P_1") (pintype "passive"))
      (node (ref "C22") (pin "2") (pinfunction "2_2") (pintype "passive"))
      (node (ref "C23") (pin "2") (pinfunction "2_2") (pintype "passive"))
      (node (ref "C25") (pin "2") (pintype "passive"))
      (node (ref "C28") (pin "2") (pinfunction "2_2") (pintype "passive"))
      (node (ref "C35") (pin "2") (pinfunction "2_2") (pintype "passive"))
      (node (ref "DS1") (pin "3") (pinfunction "VDD_3") (pintype "passive"))
      (node (ref "R21") (pin "1") (pinfunction "1_1") (pintype "passive"))
      (node (ref "R24") (pin "1") (pinfunction "1_1") (pintype "passive"))
      (node (ref "R27") (pin "1") (pinfunction "1_1") (pintype "passive"))
      (node (ref "R29") (pin "1") (pinfunction "1_1") (pintype "passive"))
      (node (ref "R31") (pin "2") (pinfunction "2_2") (pintype "passive"))
      (node (ref "R36") (pin "1") (pinfunction "1_1") (pintype "passive"))
      (node (ref "R37") (pin "1") (pinfunction "1_1") (pintype "passive"))
      (node (ref "U10") (pin "8") (pinfunction "VCC_8") (pintype "passive"))
      (node (ref "U12") (pin "3") (pinfunction "VCC_3") (pintype "passive"))
      (node (ref "U7") (pin "2") (pinfunction "VOUT_2") (pintype "passive"))
      (node (ref "U9") (pin "3") (pinfunction "VDD_3") (pintype "passive"))
    )
    (net (code "42") (name "3.3V_VFD") (class "Default")
      (node (ref "C17") (pin "2") (pinfunction "2_2") (pintype "passive"))
      (node (ref "C18") (pin "1") (pinfunction "1_1") (pintype "passive"))
      (node (ref "C19") (pin "1") (pinfunction "1_1") (pintype "passive"))
      (node (ref "C20") (pin "1") (pinfunction "1_1") (pintype "passive"))
      (node (ref "C29") (pin "2") (pinfunction "2_2") (pintype "passive"))
      (node (ref "C30") (pin "2") (pinfunction "2_2") (pintype "passive"))
      (node (ref "R26") (pin "1") (pinfunction "1_1") (pintype "passive"))
      (node (ref "U5") (pin "2") (pinfunction "VOUT_2") (pintype "passive"))
      (node (ref "V1") (pin "18") (pinfunction "3V3_18") (pintype "passive"))
      (node (ref "V1") (pin "26") (pinfunction "3V3_26") (pintype "passive"))
      (node (ref "V1") (pin "8") (pinfunction "3V3_8") (pintype "passive"))
    )
    (net (code "43") (name "3.3V_WALN") (class "Default")
      (node (ref "1") (pin "1") (pinfunction "1_1") (pintype "passive"))
      (node (ref "1") (pin "2") (pinfunction "2_2") (pintype "passive"))
      (node (ref "1") (pin "3") (pinfunction "3_3") (pintype "passive"))
      (node (ref "1") (pin "4") (pinfunction "4_4") (pintype "passive"))
      (node (ref "C31") (pin "2") (pinfunction "2_2") (pintype "passive"))
      (node (ref "C32") (pin "2") (pinfunction "2_2") (pintype "passive"))
      (node (ref "C42") (pin "2") (pinfunction "2_2") (pintype "passive"))
      (node (ref "C43") (pin "2") (pinfunction "2_2") (pintype "passive"))
      (node (ref "C44") (pin "2") (pinfunction "2_2") (pintype "passive"))
      (node (ref "C45") (pin "2") (pinfunction "2_2") (pintype "passive"))
      (node (ref "M1") (pin "8") (pinfunction "VCC_8") (pintype "passive"))
      (node (ref "P1") (pin "5") (pinfunction "5_5") (pintype "passive"))
      (node (ref "U8") (pin "2") (pinfunction "VOUT_2") (pintype "passive"))
    )
    (net (code "44") (name "F1") (class "Default")
      (node (ref "U2") (pin "8") (pinfunction "VO2_8") (pintype "passive"))
      (node (ref "V1") (pin "1") (pinfunction "F1_1") (pintype "passive"))
      (node (ref "V1") (pin "2") (pinfunction "F1_2") (pintype "passive"))
      (node (ref "V1") (pin "3") (pinfunction "F1_3") (pintype "passive"))
      (node (ref "V1") (pin "4") (pinfunction "F1_4") (pintype "passive"))
    )
    (net (code "45") (name "F2") (class "Default")
      (node (ref "R11") (pin "1") (pinfunction "1_1") (pintype "passive"))
      (node (ref "R14") (pin "2") (pinfunction "2_2") (pintype "passive"))
      (node (ref "U2") (pin "5") (pinfunction "VO1_5") (pintype "passive"))
      (node (ref "V1") (pin "28") (pinfunction "F2_28") (pintype "passive"))
      (node (ref "V1") (pin "29") (pinfunction "F2_29") (pintype "passive"))
      (node (ref "V1") (pin "30") (pinfunction "F2_30") (pintype "passive"))
      (node (ref "V1") (pin "31") (pinfunction "F2_31") (pintype "passive"))
    )
    (net (code "46") (name "GND") (class "Default")
      (node (ref "B2") (pin "2") (pinfunction "-_2") (pintype "passive"))
      (node (ref "C1") (pin "1") (pinfunction "1_1") (pintype "passive"))
      (node (ref "C10") (pin "1") (pinfunction "1_1") (pintype "passive"))
      (node (ref "C11") (pin "1") (pinfunction "1_1") (pintype "passive"))
      (node (ref "C12") (pin "1") (pinfunction "1_1") (pintype "passive"))
      (node (ref "C13") (pin "1") (pinfunction "1_1") (pintype "passive"))
      (node (ref "C14") (pin "1") (pinfunction "1_1") (pintype "passive"))
      (node (ref "C15") (pin "1") (pinfunction "1_1") (pintype "passive"))
      (node (ref "C16") (pin "1") (pinfunction "1_1") (pintype "passive"))
      (node (ref "C17") (pin "1") (pinfunction "1_1") (pintype "passive"))
      (node (ref "C18") (pin "2") (pinfunction "2_2") (pintype "passive"))
      (node (ref "C19") (pin "2") (pinfunction "2_2") (pintype "passive"))
      (node (ref "C2") (pin "1") (pinfunction "1_1") (pintype "passive"))
      (node (ref "C20") (pin "2") (pinfunction "2_2") (pintype "passive"))
      (node (ref "C21") (pin "2") (pinfunction "2_2") (pintype "passive"))
      (node (ref "C22") (pin "1") (pinfunction "1_1") (pintype "passive"))
      (node (ref "C23") (pin "1") (pinfunction "1_1") (pintype "passive"))
      (node (ref "C24") (pin "1") (pinfunction "1_1") (pintype "passive"))
      (node (ref "C25") (pin "1") (pintype "passive"))
      (node (ref "C26") (pin "1") (pinfunction "1_1") (pintype "passive"))
      (node (ref "C27") (pin "2") (pinfunction "2_2") (pintype "passive"))
      (node (ref "C28") (pin "1") (pinfunction "1_1") (pintype "passive"))
      (node (ref "C29") (pin "1") (pinfunction "1_1") (pintype "passive"))
      (node (ref "C3") (pin "1") (pinfunction "1_1") (pintype "passive"))
      (node (ref "C30") (pin "1") (pinfunction "1_1") (pintype "passive"))
      (node (ref "C31") (pin "1") (pinfunction "1_1") (pintype "passive"))
      (node (ref "C32") (pin "1") (pinfunction "1_1") (pintype "passive"))
      (node (ref "C33") (pin "1") (pinfunction "1_1") (pintype "passive"))
      (node (ref "C34") (pin "1") (pinfunction "1_1") (pintype "passive"))
      (node (ref "C35") (pin "1") (pinfunction "1_1") (pintype "passive"))
      (node (ref "C36") (pin "1") (pinfunction "1_1") (pintype "passive"))
      (node (ref "C37") (pin "1") (pinfunction "1_1") (pintype "passive"))
      (node (ref "C38") (pin "1") (pinfunction "1_1") (pintype "passive"))
      (node (ref "C39") (pin "1") (pinfunction "1_1") (pintype "passive"))
      (node (ref "C4") (pin "1") (pinfunction "1_1") (pintype "passive"))
      (node (ref "C40") (pin "1") (pinfunction "1_1") (pintype "passive"))
      (node (ref "C41") (pin "1") (pinfunction "1_1") (pintype "passive"))
      (node (ref "C42") (pin "1") (pinfunction "1_1") (pintype "passive"))
      (node (ref "C43") (pin "1") (pinfunction "1_1") (pintype "passive"))
      (node (ref "C44") (pin "1") (pinfunction "1_1") (pintype "passive"))
      (node (ref "C45") (pin "1") (pinfunction "1_1") (pintype "passive"))
      (node (ref "C46") (pin "1") (pinfunction "1_1") (pintype "passive"))
      (node (ref "C47") (pin "1") (pinfunction "1_1") (pintype "passive"))
      (node (ref "C48") (pin "1") (pinfunction "1_1") (pintype "passive"))
      (node (ref "C49") (pin "1") (pinfunction "1_1") (pintype "passive"))
      (node (ref "C5") (pin "2") (pinfunction "2_2") (pintype "passive"))
      (node (ref "C6") (pin "1") (pinfunction "1_1") (pintype "passive"))
      (node (ref "C7") (pin "1") (pinfunction "1_1") (pintype "passive"))
      (node (ref "C8") (pin "1") (pinfunction "1_1") (pintype "passive"))
      (node (ref "C9") (pin "1") (pinfunction "1_1") (pintype "passive"))
      (node (ref "D3") (pin "1") (pinfunction "A_1") (pintype "passive"))
      (node (ref "DS1") (pin "1") (pinfunction "GND_1") (pintype "passive"))
      (node (ref "E1") (pin "2") (pinfunction "2_2") (pintype "passive"))
      (node (ref "E2") (pin "2") (pinfunction "2_2") (pintype "passive"))
      (node (ref "E3") (pin "2") (pinfunction "2_2") (pintype "passive"))
      (node (ref "E4") (pin "2") (pinfunction "2_2") (pintype "passive"))
      (node (ref "E5") (pin "2") (pinfunction "2_2") (pintype "passive"))
      (node (ref "E6") (pin "2") (pinfunction "2_2") (pintype "passive"))
      (node (ref "J1") (pin "2") (pinfunction "2_2") (pintype "passive"))
      (node (ref "K1") (pin "1") (pinfunction "1_1") (pintype "passive"))
      (node (ref "M1") (pin "0") (pinfunction "GND_0") (pintype "passive"))
      (node (ref "M1") (pin "9") (pinfunction "GND_9") (pintype "passive"))
      (node (ref "P1") (pin "2") (pinfunction "2_2") (pintype "passive"))
      (node (ref "Q3") (pin "2") (pinfunction "D_2") (pintype "passive"))
      (node (ref "Q4") (pin "3") (pinfunction "C_3") (pintype "passive"))
      (node (ref "R13") (pin "1") (pinfunction "1_1") (pintype "passive"))
      (node (ref "R15") (pin "2") (pinfunction "2_2") (pintype "passive"))
      (node (ref "R16") (pin "1") (pinfunction "1_1") (pintype "passive"))
      (node (ref "R17") (pin "2") (pinfunction "2_2") (pintype "passive"))
      (node (ref "R19") (pin "2") (pinfunction "2_2") (pintype "passive"))
      (node (ref "R32") (pin "2") (pinfunction "2_2") (pintype "passive"))
      (node (ref "R8") (pin "2") (pinfunction "2_2") (pintype "passive"))
      (node (ref "R9") (pin "1") (pinfunction "1_1") (pintype "passive"))
      (node (ref "SWD1") (pin "1") (pinfunction "VCC_1") (pintype "passive"))
      (node (ref "T1") (pin "0") (pinfunction "0_0") (pintype "passive"))
      (node (ref "T1") (pin "1") (pinfunction "G_1") (pintype "passive"))
      (node (ref "T1") (pin "14") (pinfunction "G_14") (pintype "passive"))
      (node (ref "T1") (pin "7") (pinfunction "G_7") (pintype "passive"))
      (node (ref "T1") (pin "8") (pinfunction "G_8") (pintype "passive"))
      (node (ref "TVS1") (pin "2") (pinfunction "2_2") (pintype "passive"))
      (node (ref "U1") (pin "7") (pinfunction "GND_7") (pintype "passive"))
      (node (ref "U1") (pin "8") (pinfunction "GND_8") (pintype "passive"))
      (node (ref "U10") (pin "1") (pinfunction "A0_1") (pintype "passive"))
      (node (ref "U10") (pin "2") (pinfunction "A1_2") (pintype "passive"))
      (node (ref "U10") (pin "3") (pinfunction "A2_3") (pintype "passive"))
      (node (ref "U10") (pin "4") (pinfunction "GND_4") (pintype "passive"))
      (node (ref "U10") (pin "7") (pinfunction "WP_7") (pintype "passive"))
      (node (ref "U11") (pin "3") (pinfunction "GND_3") (pintype "passive"))
      (node (ref "U12") (pin "2") (pinfunction "GND_2") (pintype "passive"))
      (node (ref "U2") (pin "7") (pinfunction "GND_7") (pintype "passive"))
      (node (ref "U3") (pin "6") (pinfunction "AGND_6") (pintype "passive"))
      (node (ref "U3") (pin "7") (pinfunction "GND_7") (pintype "passive"))
      (node (ref "U4") (pin "2") (pinfunction "GND_2") (pintype "passive"))
      (node (ref "U5") (pin "1") (pinfunction "GND_1") (pintype "passive"))
      (node (ref "U6") (pin "20") (pinfunction "BOOT1/PB2_20") (pintype "bidirectional"))
      (node (ref "U6") (pin "23") (pinfunction "VSS_1_23") (pintype "power_in"))
      (node (ref "U6") (pin "35") (pinfunction "VSS_2_35") (pintype "power_in"))
      (node (ref "U6") (pin "44") (pinfunction "BOOT0_44") (pintype "input"))
      (node (ref "U6") (pin "47") (pinfunction "VSS_3_47") (pintype "power_in"))
      (node (ref "U6") (pin "8") (pinfunction "VSSA_8") (pintype "power_in"))
      (node (ref "U7") (pin "1") (pinfunction "GND_1") (pintype "passive"))
      (node (ref "U8") (pin "1") (pinfunction "GND_1") (pintype "passive"))
      (node (ref "U9") (pin "6") (pinfunction "GND_6") (pintype "passive"))
      (node (ref "V1") (pin "13") (pinfunction "GND_13") (pintype "passive"))
      (node (ref "V1") (pin "15") (pinfunction "GND_15") (pintype "passive"))
      (node (ref "V1") (pin "27") (pinfunction "GND_27") (pintype "passive"))
      (node (ref "V1") (pin "5") (pinfunction "GND_5") (pintype "passive"))
      (node (ref "V1") (pin "6") (pinfunction "GND_6") (pintype "passive"))
      (node (ref "Y1") (pin "3") (pinfunction "3_3") (pintype "passive"))
      (node (ref "key1") (pin "2") (pinfunction "2_2") (pintype "passive"))
      (node (ref "key2") (pin "2") (pinfunction "2_2") (pintype "passive"))
    )
    (net (code "47") (name "HV5") (class "Default")
      (node (ref "C1") (pin "2") (pinfunction "2_2") (pintype "passive"))
      (node (ref "C2") (pin "2") (pinfunction "2_2") (pintype "passive"))
      (node (ref "C38") (pin "2") (pinfunction "2_2") (pintype "passive"))
      (node (ref "C39") (pin "2") (pinfunction "2_2") (pintype "passive"))
      (node (ref "E1") (pin "1") (pinfunction "1_1") (pintype "passive"))
      (node (ref "E2") (pin "1") (pinfunction "1_1") (pintype "passive"))
      (node (ref "E4") (pin "1") (pinfunction "1_1") (pintype "passive"))
      (node (ref "E6") (pin "1") (pinfunction "1_1") (pintype "passive"))
      (node (ref "L1") (pin "1") (pinfunction "1_1") (pintype "passive"))
      (node (ref "L2") (pin "1") (pinfunction "1_1") (pintype "passive"))
      (node (ref "Q2") (pin "2") (pinfunction "D_2") (pintype "passive"))
      (node (ref "R1") (pin "2") (pinfunction "2_2") (pintype "passive"))
      (node (ref "R10") (pin "2") (pinfunction "2_2") (pintype "passive"))
      (node (ref "U1") (pin "2") (pinfunction "VIN_2") (pintype "passive"))
      (node (ref "U2") (pin "6") (pinfunction "VDD_6") (pintype "passive"))
      (node (ref "U3") (pin "2") (pinfunction "V+_2") (pintype "passive"))
    )
    (net (code "48") (name "HV56") (class "Default")
      (node (ref "C3") (pin "2") (pinfunction "2_2") (pintype "passive"))
      (node (ref "C48") (pin "2") (pinfunction "2_2") (pintype "passive"))
      (node (ref "C49") (pin "2") (pinfunction "2_2") (pintype "passive"))
      (node (ref "E3") (pin "1") (pinfunction "1_1") (pintype "passive"))
      (node (ref "R4") (pin "2") (pinfunction "2_2") (pintype "passive"))
      (node (ref "V1") (pin "11") (pinfunction "HV1_11") (pintype "passive"))
      (node (ref "VD2") (pin "2") (pinfunction "K_2") (pintype "passive"))
    )
    (net (code "49") (name "HV96") (class "Default")
      (node (ref "C46") (pin "2") (pinfunction "2_2") (pintype "passive"))
      (node (ref "C47") (pin "2") (pinfunction "2_2") (pintype "passive"))
      (node (ref "E5") (pin "1") (pinfunction "1_1") (pintype "passive"))
      (node (ref "R2") (pin "2") (pinfunction "2_2") (pintype "passive"))
      (node (ref "V1") (pin "7") (pinfunction "HV2_7") (pintype "passive"))
      (node (ref "VD1") (pin "2") (pinfunction "K_2") (pintype "passive"))
    )
    (net (code "50") (name "Net-(B1-G)") (class "Default")
      (node (ref "B1") (pin "2") (pinfunction "G_2") (pintype "passive"))
      (node (ref "Q4") (pin "2") (pinfunction "E_2") (pintype "passive"))
    )
    (net (code "51") (name "Net-(B2-+)") (class "Default")
      (node (ref "B2") (pin "1") (pinfunction "+_1") (pintype "passive"))
      (node (ref "D4") (pin "2") (pinfunction "K_2") (pintype "passive"))
      (node (ref "U9") (pin "5") (pinfunction "VBAT_5") (pintype "passive"))
    )
    (net (code "52") (name "Net-(D1-Pad2)") (class "Default")
      (node (ref "D1") (pin "2") (pinfunction "2_2") (pintype "passive"))
      (node (ref "R18") (pin "1") (pinfunction "1_1") (pintype "passive"))
    )
    (net (code "53") (name "Net-(D2-Pad2)") (class "Default")
      (node (ref "D2") (pin "2") (pinfunction "2_2") (pintype "passive"))
      (node (ref "R19") (pin "1") (pinfunction "1_1") (pintype "passive"))
    )
    (net (code "54") (name "Net-(D4-A)") (class "Default")
      (node (ref "D4") (pin "1") (pinfunction "A_1") (pintype "passive"))
      (node (ref "R29") (pin "2") (pinfunction "2_2") (pintype "passive"))
    )
    (net (code "55") (name "Net-(D5-K)") (class "Default")
      (node (ref "D5") (pin "2") (pinfunction "K_2") (pintype "passive"))
      (node (ref "SWD1") (pin "4") (pinfunction "SWDCLK_4") (pintype "passive"))
    )
    (net (code "56") (name "Net-(Q1-D)") (class "Default")
      (node (ref "L1") (pin "2") (pinfunction "2_2") (pintype "passive"))
      (node (ref "Q1") (pin "2") (pinfunction "D_2") (pintype "passive"))
      (node (ref "VD1") (pin "1") (pinfunction "A_1") (pintype "passive"))
    )
    (net (code "57") (name "Net-(Q1-G)") (class "Default")
      (node (ref "Q1") (pin "1") (pinfunction "G_1") (pintype "passive"))
      (node (ref "U3") (pin "1") (pinfunction "EXT_1") (pintype "output"))
    )
    (net (code "58") (name "Net-(Q1-S)") (class "Default")
      (node (ref "C5") (pin "1") (pinfunction "1_1") (pintype "passive"))
      (node (ref "Q1") (pin "3") (pinfunction "S_3") (pintype "passive"))
      (node (ref "R9") (pin "2") (pinfunction "2_2") (pintype "passive"))
      (node (ref "U3") (pin "8") (pinfunction "CS_8") (pintype "passive"))
    )
    (net (code "59") (name "Net-(Q3-G)") (class "Default")
      (node (ref "Q3") (pin "1") (pinfunction "G_1") (pintype "passive"))
      (node (ref "R6") (pin "1") (pinfunction "1_1") (pintype "passive"))
      (node (ref "R8") (pin "1") (pinfunction "1_1") (pintype "passive"))
    )
    (net (code "60") (name "Net-(Q4-B)") (class "Default")
      (node (ref "Q4") (pin "1") (pinfunction "B_1") (pintype "passive"))
      (node (ref "R22") (pin "1") (pinfunction "1_1") (pintype "passive"))
    )
    (net (code "61") (name "Net-(R7-BOT)") (class "Default")
      (node (ref "R4") (pin "1") (pinfunction "1_1") (pintype "passive"))
      (node (ref "R7") (pin "3") (pinfunction "BOT_3") (pintype "passive"))
    )
    (net (code "62") (name "Net-(R7-TAP)") (class "Default")
      (node (ref "R13") (pin "2") (pinfunction "2_2") (pintype "passive"))
      (node (ref "R7") (pin "1") (pinfunction "TOP_1") (pintype "passive"))
      (node (ref "R7") (pin "2") (pinfunction "TAP_2") (pintype "passive"))
      (node (ref "U1") (pin "3") (pinfunction "FB_3") (pintype "passive"))
    )
    (net (code "63") (name "Net-(R12-BOT)") (class "Default")
      (node (ref "R12") (pin "3") (pinfunction "BOT_3") (pintype "passive"))
      (node (ref "R2") (pin "1") (pinfunction "1_1") (pintype "passive"))
    )
    (net (code "64") (name "Net-(R12-TAP)") (class "Default")
      (node (ref "R12") (pin "1") (pinfunction "TOP_1") (pintype "passive"))
      (node (ref "R12") (pin "2") (pinfunction "TAP_2") (pintype "passive"))
      (node (ref "R16") (pin "2") (pinfunction "2_2") (pintype "passive"))
      (node (ref "U3") (pin "3") (pinfunction "FB_3") (pintype "passive"))
    )
    (net (code "65") (name "Net-(R32-Pad1)") (class "Default")
      (node (ref "R32") (pin "1") (pinfunction "1_1") (pintype "passive"))
      (node (ref "RG1") (pin "2") (pinfunction "2_2") (pintype "passive"))
    )
    (net (code "66") (name "Net-(S1-2)") (class "Default")
      (node (ref "F1") (pin "1") (pinfunction "1_1") (pintype "passive"))
      (node (ref "S1") (pin "1") (pinfunction "2_1") (pintype "passive"))
    )
    (net (code "67") (name "Net-(T1-CC1)") (class "Default")
      (node (ref "R33") (pin "1") (pinfunction "1_1") (pintype "passive"))
      (node (ref "T1") (pin "12") (pinfunction "CC1_12") (pintype "passive"))
    )
    (net (code "68") (name "Net-(U1-EN)") (class "Default")
      (node (ref "R1") (pin "1") (pinfunction "1_1") (pintype "passive"))
      (node (ref "U1") (pin "1") (pinfunction "EN_1") (pintype "input"))
    )
    (net (code "69") (name "Net-(U2-+IN)") (class "Default")
      (node (ref "R10") (pin "1") (pinfunction "1_1") (pintype "passive"))
      (node (ref "R14") (pin "1") (pinfunction "1_1") (pintype "passive"))
      (node (ref "R15") (pin "1") (pinfunction "1_1") (pintype "passive"))
      (node (ref "U2") (pin "3") (pinfunction "+IN_3") (pintype "passive"))
    )
    (net (code "70") (name "Net-(U2--IN)") (class "Default")
      (node (ref "C6") (pin "2") (pinfunction "2_2") (pintype "passive"))
      (node (ref "R11") (pin "2") (pinfunction "2_2") (pintype "passive"))
      (node (ref "U2") (pin "4") (pinfunction "-IN_4") (pintype "passive"))
    )
    (net (code "71") (name "Net-(U2-BYPASS)") (class "Default")
      (node (ref "C4") (pin "2") (pinfunction "2_2") (pintype "passive"))
      (node (ref "U2") (pin "2") (pinfunction "BYPASS_2") (pintype "passive"))
    )
    (net (code "72") (name "Net-(U2-SHDN)") (class "Default")
      (node (ref "R5") (pin "1") (pinfunction "1_1") (pintype "passive"))
      (node (ref "U2") (pin "1") (pinfunction "SHDN_1") (pintype "input"))
    )
    (net (code "73") (name "Net-(U3-REF)") (class "Default")
      (node (ref "C7") (pin "2") (pinfunction "2_2") (pintype "passive"))
      (node (ref "U3") (pin "5") (pinfunction "REF_5") (pintype "passive"))
    )
    (net (code "74") (name "Net-(U3-SHDN)") (class "Default")
      (node (ref "R17") (pin "1") (pinfunction "1_1") (pintype "passive"))
      (node (ref "U3") (pin "4") (pinfunction "SHDN_4") (pintype "passive"))
    )
    (net (code "75") (name "Net-(U4-BP)") (class "Default")
      (node (ref "C15") (pin "2") (pinfunction "2_2") (pintype "passive"))
      (node (ref "U4") (pin "4") (pinfunction "BP_4") (pintype "passive"))
    )
    (net (code "76") (name "Net-(U6-OSC_OUT)") (class "Default")
      (node (ref "U6") (pin "6") (pinfunction "OSC_OUT_6") (pintype "output"))
      (node (ref "Y1") (pin "1") (pinfunction "OSC1_1") (pintype "passive"))
    )
    (net (code "77") (name "Net-(U11-RXD)") (class "Default")
      (node (ref "R38") (pin "1") (pinfunction "1_1") (pintype "passive"))
      (node (ref "U11") (pin "7") (pinfunction "RXD_7") (pintype "passive"))
    )
    (net (code "78") (name "Net-(U11-TXD)") (class "Default")
      (node (ref "R39") (pin "1") (pinfunction "1_1") (pintype "passive"))
      (node (ref "U11") (pin "6") (pinfunction "TXD_6") (pintype "passive"))
    )
    (net (code "79") (name "Net-(U11-V3)") (class "Default")
      (node (ref "C24") (pin "2") (pinfunction "2_2") (pintype "passive"))
      (node (ref "U11") (pin "8") (pinfunction "V3_8") (pintype "passive"))
    )
    (net (code "80") (name "Net-(VD2-A)") (class "Default")
      (node (ref "L2") (pin "2") (pinfunction "2_2") (pintype "passive"))
      (node (ref "U1") (pin "5") (pinfunction "SW_5") (pintype "passive"))
      (node (ref "U1") (pin "6") (pinfunction "SW_6") (pintype "passive"))
      (node (ref "VD2") (pin "1") (pinfunction "A_1") (pintype "passive"))
    )
    (net (code "81") (name "USB_5V") (class "Default")
      (node (ref "C27") (pin "1") (pinfunction "1_1") (pintype "passive"))
      (node (ref "F1") (pin "2") (pinfunction "2_2") (pintype "passive"))
      (node (ref "J1") (pin "1") (pinfunction "1_1") (pintype "passive"))
      (node (ref "R33") (pin "2") (pinfunction "2_2") (pintype "passive"))
      (node (ref "T1") (pin "13") (pinfunction "V_13") (pintype "passive"))
      (node (ref "T1") (pin "2") (pinfunction "V_2") (pintype "passive"))
      (node (ref "T1") (pin "6") (pinfunction "V_6") (pintype "passive"))
      (node (ref "T1") (pin "9") (pinfunction "V_9") (pintype "passive"))
      (node (ref "U11") (pin "5") (pinfunction "VCC_5") (pintype "passive"))
    )
    (net (code "82") (name "VC5") (class "Default")
      (node (ref "C13") (pin "2") (pinfunction "2_2") (pintype "passive"))
      (node (ref "C14") (pin "2") (pinfunction "2_2") (pintype "passive"))
      (node (ref "C33") (pin "2") (pinfunction "2_2") (pintype "passive"))
      (node (ref "C34") (pin "2") (pinfunction "2_2") (pintype "passive"))
      (node (ref "C40") (pin "2") (pinfunction "2_2") (pintype "passive"))
      (node (ref "C41") (pin "2") (pinfunction "2_2") (pintype "passive"))
      (node (ref "D3") (pin "2") (pinfunction "K_2") (pintype "passive"))
      (node (ref "Q2") (pin "3") (pinfunction "S_3") (pintype "passive"))
      (node (ref "R3") (pin "2") (pinfunction "2_2") (pintype "passive"))
      (node (ref "S1") (pin "2") (pinfunction "1_2") (pintype "passive"))
      (node (ref "TVS1") (pin "1") (pinfunction "1_1") (pintype "passive"))
      (node (ref "U4") (pin "1") (pinfunction "VIN_1") (pintype "passive"))
      (node (ref "U4") (pin "3") (pinfunction "EN_3") (pintype "passive"))
      (node (ref "U5") (pin "3") (pinfunction "VIN_3") (pintype "passive"))
      (node (ref "U7") (pin "3") (pinfunction "VIN_3") (pintype "passive"))
      (node (ref "U8") (pin "3") (pinfunction "VIN_3") (pintype "passive"))
    )
    (net (code "83") (name "unconnected-(2-Pad6)") (class "Default")
      (node (ref "2") (pin "6") (pinfunction "6_6") (pintype "passive+no_connect"))
    )
    (net (code "84") (name "unconnected-(M1-ADC-Pad2)") (class "Default")
      (node (ref "M1") (pin "2") (pinfunction "ADC_2") (pintype "passive"))
    )
    (net (code "85") (name "unconnected-(M1-GPIO0-Pad12)") (class "Default")
      (node (ref "M1") (pin "12") (pinfunction "GPIO0_12") (pintype "passive+no_connect"))
    )
    (net (code "86") (name "unconnected-(M1-GPIO2-Pad11)") (class "Default")
      (node (ref "M1") (pin "11") (pinfunction "GPIO2_11") (pintype "passive+no_connect"))
    )
    (net (code "87") (name "unconnected-(M1-GPIO4-Pad13)") (class "Default")
      (node (ref "M1") (pin "13") (pinfunction "GPIO4_13") (pintype "passive+no_connect"))
    )
    (net (code "88") (name "unconnected-(M1-GPIO5-Pad14)") (class "Default")
      (node (ref "M1") (pin "14") (pinfunction "GPIO5_14") (pintype "passive+no_connect"))
    )
    (net (code "89") (name "unconnected-(M1-GPIO12-Pad6)") (class "Default")
      (node (ref "M1") (pin "6") (pinfunction "GPIO12_6") (pintype "passive+no_connect"))
    )
    (net (code "90") (name "unconnected-(M1-GPIO13-Pad7)") (class "Default")
      (node (ref "M1") (pin "7") (pinfunction "GPIO13_7") (pintype "passive+no_connect"))
    )
    (net (code "91") (name "unconnected-(M1-GPIO14-Pad5)") (class "Default")
      (node (ref "M1") (pin "5") (pinfunction "GPIO14_5") (pintype "passive+no_connect"))
    )
    (net (code "92") (name "unconnected-(M1-GPIO15-Pad10)") (class "Default")
      (node (ref "M1") (pin "10") (pinfunction "GPIO15_10") (pintype "passive+no_connect"))
    )
    (net (code "93") (name "unconnected-(M1-GPIO16-Pad4)") (class "Default")
      (node (ref "M1") (pin "4") (pinfunction "GPIO16_4") (pintype "passive+no_connect"))
    )
    (net (code "94") (name "unconnected-(S1-4-Pad5)") (class "Default")
      (node (ref "S1") (pin "5") (pinfunction "4_5") (pintype "passive+no_connect"))
    )
    (net (code "95") (name "unconnected-(S1-5-Pad4)") (class "Default")
      (node (ref "S1") (pin "4") (pinfunction "5_4") (pintype "passive+no_connect"))
    )
    (net (code "96") (name "unconnected-(S1-6-Pad4)") (class "Default")
      (node (ref "S1") (pin "4") (pinfunction "6_4") (pintype "passive+no_connect"))
    )
    (net (code "97") (name "unconnected-(S1-Pad3)") (class "Default")
      (node (ref "S1") (pin "3") (pinfunction "3_3") (pintype "passive+no_connect"))
    )
    (net (code "98") (name "unconnected-(T1-CC2-Pad5)") (class "Default")
      (node (ref "T1") (pin "5") (pinfunction "CC2_5") (pintype "passive+no_connect"))
    )
    (net (code "99") (name "unconnected-(U1-NC-Pad4)") (class "Default")
      (node (ref "U1") (pin "4") (pinfunction "NC_4") (pintype "passive+no_connect"))
    )
    (net (code "100") (name "unconnected-(U6-JNTRST{slash}PB4-Pad40)") (class "Default")
      (node (ref "U6") (pin "40") (pinfunction "JNTRST/PB4_40") (pintype "bidirectional+no_connect"))
    )
    (net (code "101") (name "unconnected-(U6-JTDO{slash}PB3-Pad39)") (class "Default")
      (node (ref "U6") (pin "39") (pinfunction "JTDO/PB3_39") (pintype "bidirectional+no_connect"))
    )
    (net (code "102") (name "unconnected-(U6-PA6{slash}SPI1_MISO{slash}ADC12_IN6{slash}TIM3_CH1-Pad16)") (class "Default")
      (node (ref "U6") (pin "16") (pinfunction "PA6/SPI1_MISO/ADC12_IN6/TIM3_CH1_16") (pintype "bidirectional+no_connect"))
    )
    (net (code "103") (name "unconnected-(U6-PA15{slash}JTDI-Pad38)") (class "Default")
      (node (ref "U6") (pin "38") (pinfunction "PA15/JTDI_38") (pintype "bidirectional+no_connect"))
    )
    (net (code "104") (name "unconnected-(U6-PC13-TAMPER-RTC-Pad2)") (class "Default")
      (node (ref "U6") (pin "2") (pinfunction "PC13-TAMPER-RTC_2") (pintype "bidirectional+no_connect"))
    )
    (net (code "105") (name "unconnected-(U6-PC14-OSC32_IN-Pad3)") (class "Default")
      (node (ref "U6") (pin "3") (pinfunction "PC14-OSC32_IN_3") (pintype "bidirectional+no_connect"))
    )
    (net (code "106") (name "unconnected-(U6-PC15-OSC32_OUT-Pad4)") (class "Default")
      (node (ref "U6") (pin "4") (pinfunction "PC15-OSC32_OUT_4") (pintype "bidirectional+no_connect"))
    )
    (net (code "107") (name "unconnected-(U6-VBAT-Pad1)") (class "Default")
      (node (ref "U6") (pin "1") (pinfunction "VBAT_1") (pintype "power_in+no_connect"))
    )
    (net (code "108") (name "unconnected-(U9-F32K-Pad2)") (class "Default")
      (node (ref "U9") (pin "2") (pinfunction "F32K_2") (pintype "passive+no_connect"))
    )
    (net (code "109") (name "unconnected-(U9-NC-Pad4)") (class "Default")
      (node (ref "U9") (pin "4") (pinfunction "NC_4") (pintype "passive+no_connect"))
    )
    (net (code "110") (name "unconnected-(U11-RTS#-Pad4)") (class "Default")
      (node (ref "U11") (pin "4") (pinfunction "RTS#_4") (pintype "passive+no_connect"))
    )
    (net (code "111") (name "unconnected-(V1-NC-Pad9)") (class "Default")
      (node (ref "V1") (pin "9") (pinfunction "NC_9") (pintype "passive+no_connect"))
    )
    (net (code "112") (name "unconnected-(V1-NC-Pad10)") (class "Default")
      (node (ref "V1") (pin "10") (pinfunction "NC_10") (pintype "passive+no_connect"))
    )
    (net (code "113") (name "unconnected-(V1-NC-Pad12)") (class "Default")
      (node (ref "V1") (pin "12") (pinfunction "NC_12") (pintype "passive+no_connect"))
    )
    (net (code "114") (name "unconnected-(V1-NC-Pad14)") (class "Default")
      (node (ref "V1") (pin "14") (pinfunction "NC_14") (pintype "passive+no_connect"))
    )
    (net (code "115") (name "unconnected-(V1-NC-Pad16)") (class "Default")
      (node (ref "V1") (pin "16") (pinfunction "NC_16") (pintype "passive+no_connect"))
    )
    (net (code "116") (name "unconnected-(V1-NC-Pad17)") (class "Default")
      (node (ref "V1") (pin "17") (pinfunction "NC_17") (pintype "passive+no_connect"))
    )
    (net (code "117") (name "unconnected-(V1-NC-Pad24)") (class "Default")
      (node (ref "V1") (pin "24") (pinfunction "NC_24") (pintype "passive+no_connect"))
    )
    (net (code "118") (name "unconnected-(V1-NC-Pad25)") (class "Default")
      (node (ref "V1") (pin "25") (pinfunction "NC_25") (pintype "passive+no_connect"))
    )
  )
)
